# 10_-FPGA_Bank_3_Interface.net
KiCad netlist of a schematic drawn in Altium Designer
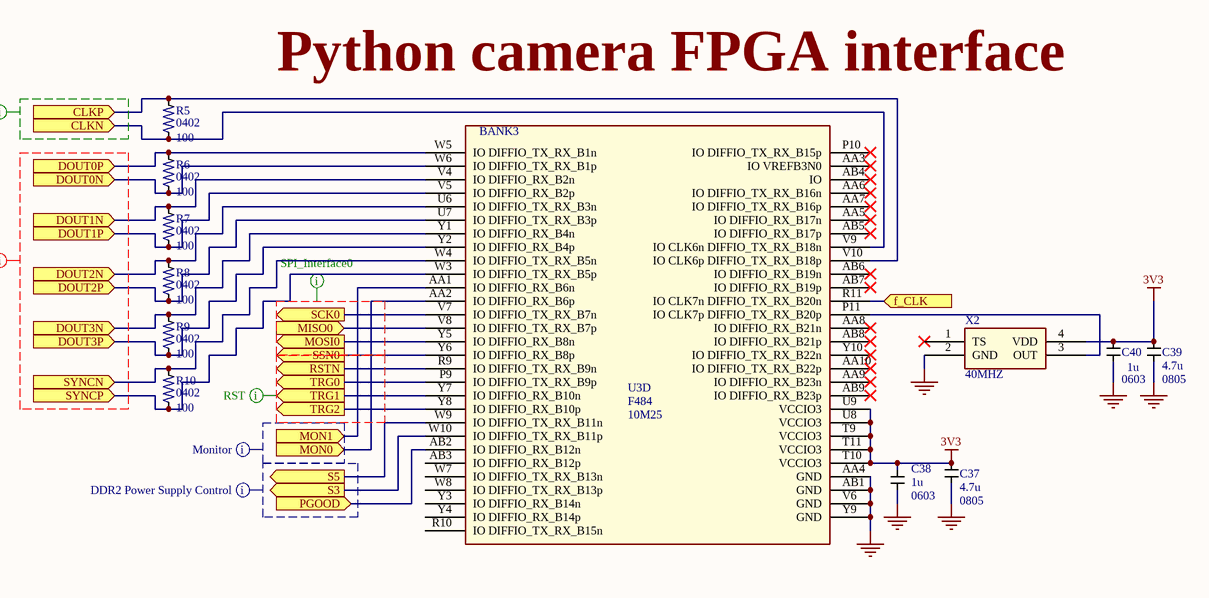
[diagram p0: [10]-FPGA_Bank_3_Interface.SchDoc]

(export (version "E")
  (design (tool "Eeschema 10.0.6"))
  (components
    (comp (ref "C37")
      (value "4.7u")
      (footprint "*CAPC2013X140N")
      (fields (field (name "PCB PACKAGE") "0805"))
      (libsource (lib "08053D475KAT2A") (part "Component_1"))
    )
    (comp (ref "C38")
      (value "1u")
      (footprint "*0603")
      (fields (field (name "PCB LAYER:") "0603"))
      (libsource (lib "0603YC105KAT2A") (part "Component_1"))
    )
    (comp (ref "C39")
      (value "4.7u")
      (footprint "*CAPC2013X140N")
      (fields (field (name "PCB PACKAGE") "0805"))
      (libsource (lib "08053D475KAT2A") (part "Component_1"))
    )
    (comp (ref "C40")
      (value "1u")
      (footprint "*0603")
      (fields (field (name "PCB LAYER:") "0603"))
      (libsource (lib "0603YC105KAT2A") (part "Component_1"))
    )
    (comp (ref "R5")
      (value "100")
      (footprint "*R0402")
      (description "Res Thin Film 0603 76.8 Ohm 0.1% 1/10W Â±15ppm/Â°C Molded SMD Paper T/R")
      (fields (field (name "PCB FOOTPRINT") "0402"))
      (libsource (lib "SMD-RES-100K-1_-1_16W_0402_") (part "RP73D1J76R8BTDG"))
    )
    (comp (ref "R6")
      (value "100")
      (footprint "*R0402")
      (description "Res Thin Film 0603 76.8 Ohm 0.1% 1/10W Â±15ppm/Â°C Molded SMD Paper T/R")
      (fields (field (name "PCB FOOTPRINT") "0402"))
      (libsource (lib "SMD-RES-100K-1_-1_16W_0402_") (part "RP73D1J76R8BTDG"))
    )
    (comp (ref "R7")
      (value "100")
      (footprint "*R0402")
      (description "Res Thin Film 0603 76.8 Ohm 0.1% 1/10W Â±15ppm/Â°C Molded SMD Paper T/R")
      (fields (field (name "PCB FOOTPRINT") "0402"))
      (libsource (lib "SMD-RES-100K-1_-1_16W_0402_") (part "RP73D1J76R8BTDG"))
    )
    (comp (ref "R8")
      (value "100")
      (footprint "*R0402")
      (description "Res Thin Film 0603 76.8 Ohm 0.1% 1/10W Â±15ppm/Â°C Molded SMD Paper T/R")
      (fields (field (name "PCB FOOTPRINT") "0402"))
      (libsource (lib "SMD-RES-100K-1_-1_16W_0402_") (part "RP73D1J76R8BTDG"))
    )
    (comp (ref "R9")
      (value "100")
      (footprint "*R0402")
      (description "Res Thin Film 0603 76.8 Ohm 0.1% 1/10W Â±15ppm/Â°C Molded SMD Paper T/R")
      (fields (field (name "PCB FOOTPRINT") "0402"))
      (libsource (lib "SMD-RES-100K-1_-1_16W_0402_") (part "RP73D1J76R8BTDG"))
    )
    (comp (ref "R10")
      (value "100")
      (footprint "*R0402")
      (description "Res Thin Film 0603 76.8 Ohm 0.1% 1/10W Â±15ppm/Â°C Molded SMD Paper T/R")
      (fields (field (name "PCB FOOTPRINT") "0402"))
      (libsource (lib "SMD-RES-100K-1_-1_16W_0402_") (part "RP73D1J76R8BTDG"))
    )
    (comp (ref "U3")
      (value "10M25")
      (footprint "*BGA484C100P22X22_2300X2300X200N")
      (fields (field (name "PART NO.") "10M25DAF484I7G") (field (name "PACKAGE TYPE") "F484"))
      (libsource (lib "10M25DAF484I7G") (part "Component_1"))
    )
    (comp (ref "X2")
      (value "40MHZ")
      (footprint "OSC_DSC6083CI2A-032K768")
      (fields (field (name "MF_PART NO.") "DSC1001CL5-040.0000"))
      (libsource (lib "DSC1001CL5-040.0000") (part "Component_1"))
    )
  )
  (nets
    (net (code "1") (name "/CLKN") (class "Default")
      (node (ref "R5") (pin "1") (pinfunction "1_1") (pintype "passive"))
      (node (ref "U3") (pin "V9") (pinfunction "IO_CLK6n_DIFFIO_TX_RX_B18n_V9") (pintype "passive"))
    )
    (net (code "2") (name "/CLKP") (class "Default")
      (node (ref "R5") (pin "2") (pinfunction "2_2") (pintype "passive"))
      (node (ref "U3") (pin "V10") (pinfunction "IO_CLK6p_DIFFIO_TX_RX_B18p_V10") (pintype "passive"))
    )
    (net (code "3") (name "/DOUT0N") (class "Default")
      (node (ref "R6") (pin "1") (pinfunction "1_1") (pintype "passive"))
      (node (ref "U3") (pin "W6") (pinfunction "IO_DIFFIO_TX_RX_B1p_W6") (pintype "passive"))
    )
    (net (code "4") (name "/DOUT0P") (class "Default")
      (node (ref "R6") (pin "2") (pinfunction "2_2") (pintype "passive"))
      (node (ref "U3") (pin "W5") (pinfunction "IO_DIFFIO_TX_RX_B1n_W5") (pintype "passive"))
    )
    (net (code "5") (name "/DOUT1N") (class "Default")
      (node (ref "R7") (pin "2") (pinfunction "2_2") (pintype "passive"))
      (node (ref "U3") (pin "V4") (pinfunction "IO_DIFFIO_RX_B2n_V4") (pintype "passive"))
    )
    (net (code "6") (name "/DOUT1P") (class "Default")
      (node (ref "R7") (pin "1") (pinfunction "1_1") (pintype "passive"))
      (node (ref "U3") (pin "V5") (pinfunction "IO_DIFFIO_RX_B2p_V5") (pintype "passive"))
    )
    (net (code "7") (name "/DOUT2N") (class "Default")
      (node (ref "R8") (pin "2") (pinfunction "2_2") (pintype "passive"))
      (node (ref "U3") (pin "U6") (pinfunction "IO_DIFFIO_TX_RX_B3n_U6") (pintype "passive"))
    )
    (net (code "8") (name "/DOUT2P") (class "Default")
      (node (ref "R8") (pin "1") (pinfunction "1_1") (pintype "passive"))
      (node (ref "U3") (pin "U7") (pinfunction "IO_DIFFIO_TX_RX_B3p_U7") (pintype "passive"))
    )
    (net (code "9") (name "/DOUT3N") (class "Default")
      (node (ref "R9") (pin "2") (pinfunction "2_2") (pintype "passive"))
      (node (ref "U3") (pin "Y1") (pinfunction "IO_DIFFIO_RX_B4n_Y1") (pintype "passive"))
    )
    (net (code "10") (name "/DOUT3P") (class "Default")
      (node (ref "R9") (pin "1") (pinfunction "1_1") (pintype "passive"))
      (node (ref "U3") (pin "Y2") (pinfunction "IO_DIFFIO_RX_B4p_Y2") (pintype "passive"))
    )
    (net (code "11") (name "/MISO0") (class "Default")
      (node (ref "U3") (pin "V8") (pinfunction "IO_DIFFIO_TX_RX_B7p_V8") (pintype "passive"))
    )
    (net (code "12") (name "/MON0") (class "Default")
      (node (ref "U3") (pin "AA2") (pinfunction "IO_DIFFIO_RX_B6p_AA2") (pintype "passive"))
    )
    (net (code "13") (name "/MON1") (class "Default")
      (node (ref "U3") (pin "AA1") (pinfunction "IO_DIFFIO_RX_B6n_AA1") (pintype "passive"))
    )
    (net (code "14") (name "/MOSI0") (class "Default")
      (node (ref "U3") (pin "Y5") (pinfunction "IO_DIFFIO_RX_B8n_Y5") (pintype "passive"))
    )
    (net (code "15") (name "/PGOOD") (class "Default")
      (node (ref "U3") (pin "AB2") (pinfunction "IO_DIFFIO_RX_B12n_AB2") (pintype "passive"))
    )
    (net (code "16") (name "/RSTN") (class "Default")
      (node (ref "U3") (pin "R9") (pinfunction "IO_DIFFIO_TX_RX_B9n_R9") (pintype "passive"))
    )
    (net (code "17") (name "/S3") (class "Default")
      (node (ref "U3") (pin "W10") (pinfunction "IO_DIFFIO_TX_RX_B11p_W10") (pintype "passive"))
    )
    (net (code "18") (name "/S5") (class "Default")
      (node (ref "U3") (pin "W9") (pinfunction "IO_DIFFIO_TX_RX_B11n_W9") (pintype "passive"))
    )
    (net (code "19") (name "/SCK0") (class "Default")
      (node (ref "U3") (pin "V7") (pinfunction "IO_DIFFIO_TX_RX_B7n_V7") (pintype "passive"))
    )
    (net (code "20") (name "/SSN0") (class "Default")
      (node (ref "U3") (pin "Y6") (pinfunction "IO_DIFFIO_RX_B8p_Y6") (pintype "passive"))
    )
    (net (code "21") (name "/SYNCN") (class "Default")
      (node (ref "R10") (pin "2") (pinfunction "2_2") (pintype "passive"))
      (node (ref "U3") (pin "W4") (pinfunction "IO_DIFFIO_TX_RX_B5n_W4") (pintype "passive"))
    )
    (net (code "22") (name "/SYNCP") (class "Default")
      (node (ref "R10") (pin "1") (pinfunction "1_1") (pintype "passive"))
      (node (ref "U3") (pin "W3") (pinfunction "IO_DIFFIO_TX_RX_B5p_W3") (pintype "passive"))
    )
    (net (code "23") (name "/TRG0") (class "Default")
      (node (ref "U3") (pin "P9") (pinfunction "IO_DIFFIO_TX_RX_B9p_P9") (pintype "passive"))
    )
    (net (code "24") (name "/TRG1") (class "Default")
      (node (ref "U3") (pin "Y7") (pinfunction "IO_DIFFIO_RX_B10n_Y7") (pintype "passive"))
    )
    (net (code "25") (name "/TRG2") (class "Default")
      (node (ref "U3") (pin "Y8") (pinfunction "IO_DIFFIO_RX_B10p_Y8") (pintype "passive"))
    )
    (net (code "26") (name "/f_CLK") (class "Default")
      (node (ref "U3") (pin "R11") (pinfunction "IO_CLK7n_DIFFIO_TX_RX_B20n_R11") (pintype "passive"))
    )
    (net (code "27") (name "3V3") (class "Default")
      (node (ref "C37") (pin "2") (pinfunction "2_2") (pintype "passive"))
      (node (ref "C38") (pin "2") (pinfunction "2_2") (pintype "passive"))
      (node (ref "C39") (pin "2") (pinfunction "2_2") (pintype "passive"))
      (node (ref "C40") (pin "2") (pinfunction "2_2") (pintype "passive"))
      (node (ref "U3") (pin "T10") (pinfunction "VCCIO3_T10") (pintype "passive"))
      (node (ref "U3") (pin "T11") (pinfunction "VCCIO3_T11") (pintype "passive"))
      (node (ref "U3") (pin "T9") (pinfunction "VCCIO3_T9") (pintype "passive"))
      (node (ref "U3") (pin "U8") (pinfunction "VCCIO3_U8") (pintype "passive"))
      (node (ref "U3") (pin "U9") (pinfunction "VCCIO3_U9") (pintype "passive"))
      (node (ref "X2") (pin "4") (pinfunction "VDD_4") (pintype "passive"))
    )
    (net (code "28") (name "GND") (class "Default")
      (node (ref "C37") (pin "1") (pinfunction "1_1") (pintype "passive"))
      (node (ref "C38") (pin "1") (pinfunction "1_1") (pintype "passive"))
      (node (ref "C39") (pin "1") (pinfunction "1_1") (pintype "passive"))
      (node (ref "C40") (pin "1") (pinfunction "1_1") (pintype "passive"))
      (node (ref "U3") (pin "AA4") (pinfunction "GND_AA4") (pintype "passive"))
      (node (ref "U3") (pin "AB1") (pinfunction "GND_AB1") (pintype "passive"))
      (node (ref "U3") (pin "V6") (pinfunction "GND_V6") (pintype "passive"))
      (node (ref "U3") (pin "Y9") (pinfunction "GND_Y9") (pintype "passive"))
      (node (ref "X2") (pin "2") (pinfunction "GND_2") (pintype "passive"))
    )
    (net (code "29") (name "Net-(U3D-IO_CLK7p_DIFFIO_TX_RX_B20p)") (class "Default")
      (node (ref "U3") (pin "P11") (pinfunction "IO_CLK7p_DIFFIO_TX_RX_B20p_P11") (pintype "passive"))
      (node (ref "X2") (pin "3") (pinfunction "OUT_3") (pintype "passive"))
    )
    (net (code "30") (name "unconnected-(U3D-IO-PadAB4)") (class "Default")
      (node (ref "U3") (pin "AB4") (pinfunction "IO_AB4") (pintype "passive+no_connect"))
    )
    (net (code "31") (name "unconnected-(U3D-IO_DIFFIO_RX_B12p-PadAB3)") (class "Default")
      (node (ref "U3") (pin "AB3") (pinfunction "IO_DIFFIO_RX_B12p_AB3") (pintype "passive"))
    )
    (net (code "32") (name "unconnected-(U3D-IO_DIFFIO_RX_B14n-PadY3)") (class "Default")
      (node (ref "U3") (pin "Y3") (pinfunction "IO_DIFFIO_RX_B14n_Y3") (pintype "passive"))
    )
    (net (code "33") (name "unconnected-(U3D-IO_DIFFIO_RX_B14p-PadY4)") (class "Default")
      (node (ref "U3") (pin "Y4") (pinfunction "IO_DIFFIO_RX_B14p_Y4") (pintype "passive"))
    )
    (net (code "34") (name "unconnected-(U3D-IO_DIFFIO_RX_B17n-PadAA5)") (class "Default")
      (node (ref "U3") (pin "AA5") (pinfunction "IO_DIFFIO_RX_B17n_AA5") (pintype "passive+no_connect"))
    )
    (net (code "35") (name "unconnected-(U3D-IO_DIFFIO_RX_B17p-PadAB5)") (class "Default")
      (node (ref "U3") (pin "AB5") (pinfunction "IO_DIFFIO_RX_B17p_AB5") (pintype "passive+no_connect"))
    )
    (net (code "36") (name "unconnected-(U3D-IO_DIFFIO_RX_B19n-PadAB6)") (class "Default")
      (node (ref "U3") (pin "AB6") (pinfunction "IO_DIFFIO_RX_B19n_AB6") (pintype "passive+no_connect"))
    )
    (net (code "37") (name "unconnected-(U3D-IO_DIFFIO_RX_B19p-PadAB7)") (class "Default")
      (node (ref "U3") (pin "AB7") (pinfunction "IO_DIFFIO_RX_B19p_AB7") (pintype "passive+no_connect"))
    )
    (net (code "38") (name "unconnected-(U3D-IO_DIFFIO_RX_B21n-PadAA8)") (class "Default")
      (node (ref "U3") (pin "AA8") (pinfunction "IO_DIFFIO_RX_B21n_AA8") (pintype "passive+no_connect"))
    )
    (net (code "39") (name "unconnected-(U3D-IO_DIFFIO_RX_B21p-PadAB8)") (class "Default")
      (node (ref "U3") (pin "AB8") (pinfunction "IO_DIFFIO_RX_B21p_AB8") (pintype "passive+no_connect"))
    )
    (net (code "40") (name "unconnected-(U3D-IO_DIFFIO_RX_B23n-PadAA9)") (class "Default")
      (node (ref "U3") (pin "AA9") (pinfunction "IO_DIFFIO_RX_B23n_AA9") (pintype "passive+no_connect"))
    )
    (net (code "41") (name "unconnected-(U3D-IO_DIFFIO_RX_B23p-PadAB9)") (class "Default")
      (node (ref "U3") (pin "AB9") (pinfunction "IO_DIFFIO_RX_B23p_AB9") (pintype "passive+no_connect"))
    )
    (net (code "42") (name "unconnected-(U3D-IO_DIFFIO_TX_RX_B13n-PadW7)") (class "Default")
      (node (ref "U3") (pin "W7") (pinfunction "IO_DIFFIO_TX_RX_B13n_W7") (pintype "passive"))
    )
    (net (code "43") (name "unconnected-(U3D-IO_DIFFIO_TX_RX_B13p-PadW8)") (class "Default")
      (node (ref "U3") (pin "W8") (pinfunction "IO_DIFFIO_TX_RX_B13p_W8") (pintype "passive"))
    )
    (net (code "44") (name "unconnected-(U3D-IO_DIFFIO_TX_RX_B15n-PadR10)") (class "Default")
      (node (ref "U3") (pin "R10") (pinfunction "IO_DIFFIO_TX_RX_B15n_R10") (pintype "passive"))
    )
    (net (code "45") (name "unconnected-(U3D-IO_DIFFIO_TX_RX_B15p-PadP10)") (class "Default")
      (node (ref "U3") (pin "P10") (pinfunction "IO_DIFFIO_TX_RX_B15p_P10") (pintype "passive+no_connect"))
    )
    (net (code "46") (name "unconnected-(U3D-IO_DIFFIO_TX_RX_B16n-PadAA6)") (class "Default")
      (node (ref "U3") (pin "AA6") (pinfunction "IO_DIFFIO_TX_RX_B16n_AA6") (pintype "passive+no_connect"))
    )
    (net (code "47") (name "unconnected-(U3D-IO_DIFFIO_TX_RX_B16p-PadAA7)") (class "Default")
      (node (ref "U3") (pin "AA7") (pinfunction "IO_DIFFIO_TX_RX_B16p_AA7") (pintype "passive+no_connect"))
    )
    (net (code "48") (name "unconnected-(U3D-IO_DIFFIO_TX_RX_B22n-PadY10)") (class "Default")
      (node (ref "U3") (pin "Y10") (pinfunction "IO_DIFFIO_TX_RX_B22n_Y10") (pintype "passive+no_connect"))
    )
    (net (code "49") (name "unconnected-(U3D-IO_DIFFIO_TX_RX_B22p-PadAA10)") (class "Default")
      (node (ref "U3") (pin "AA10") (pinfunction "IO_DIFFIO_TX_RX_B22p_AA10") (pintype "passive+no_connect"))
    )
    (net (code "50") (name "unconnected-(U3D-IO_VREFB3N0-PadAA3)") (class "Default")
      (node (ref "U3") (pin "AA3") (pinfunction "IO_VREFB3N0_AA3") (pintype "passive+no_connect"))
    )
    (net (code "51") (name "unconnected-(X2-TS-Pad1)") (class "Default")
      (node (ref "X2") (pin "1") (pinfunction "TS_1") (pintype "passive+no_connect"))
    )
  )
)
